# MPU-6050-HMC-5883.net
KiCad netlist of a schematic drawn in EAGLE
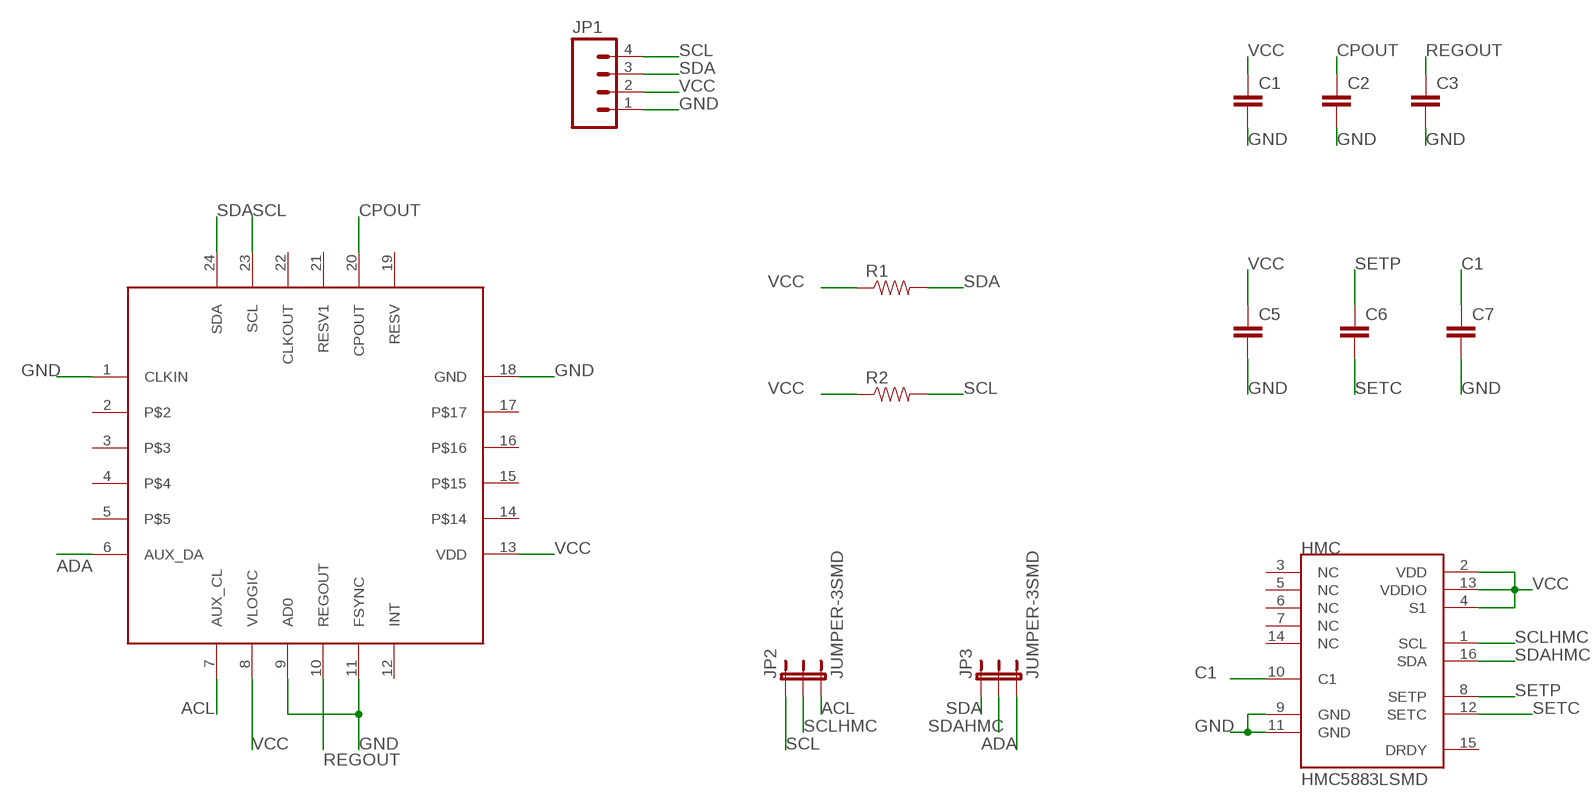
[diagram p0: schematic, sheet 1]

(export (version "E")
  (design (tool "Eeschema 10.0.6"))
  (components
    (comp (ref "C1")
      (value "CAP0603-CAP")
      (footprint "eagle-import:0603-CAP")
      (libsource (lib "eagle-import") (part "CAP0603-CAP"))
    )
    (comp (ref "C2")
      (value "CAP0603-CAP")
      (footprint "eagle-import:0603-CAP")
      (libsource (lib "eagle-import") (part "CAP0603-CAP"))
    )
    (comp (ref "C3")
      (value "CAP0603-CAP")
      (footprint "eagle-import:0603-CAP")
      (libsource (lib "eagle-import") (part "CAP0603-CAP"))
    )
    (comp (ref "C5")
      (value "CAP0603-CAP")
      (footprint "eagle-import:0603-CAP")
      (libsource (lib "eagle-import") (part "CAP0603-CAP"))
    )
    (comp (ref "C6")
      (value "CAP0603-CAP")
      (footprint "eagle-import:0603-CAP")
      (libsource (lib "eagle-import") (part "CAP0603-CAP"))
    )
    (comp (ref "C7")
      (value "CAP0603-CAP")
      (footprint "eagle-import:0603-CAP")
      (libsource (lib "eagle-import") (part "CAP0603-CAP"))
    )
    (comp (ref "HMC")
      (value "HMC5883LSMD")
      (footprint "eagle-import:16LPCC")
      (libsource (lib "eagle-import") (part "HMC5883LSMD"))
    )
    (comp (ref "JP1")
      (value "M04PTH")
      (footprint "eagle-import:1X04")
      (libsource (lib "eagle-import") (part "M04PTH"))
    )
    (comp (ref "JP2")
      (value "JUMPER-3SMD")
      (footprint "eagle-import:SJ_3")
      (libsource (lib "eagle-import") (part "JUMPER-3SMD"))
    )
    (comp (ref "JP3")
      (value "JUMPER-3SMD")
      (footprint "eagle-import:SJ_3")
      (libsource (lib "eagle-import") (part "JUMPER-3SMD"))
    )
    (comp (ref "MPU")
      (value "MPU-6050")
      (footprint "eagle-import:QFN-24")
      (libsource (lib "eagle-import") (part "MPU-6050"))
    )
    (comp (ref "R1")
      (value "RESISTOR0603-RES")
      (footprint "eagle-import:0603-RES")
      (libsource (lib "eagle-import") (part "RESISTOR0603-RES"))
    )
    (comp (ref "R2")
      (value "RESISTOR0603-RES")
      (footprint "eagle-import:0603-RES")
      (libsource (lib "eagle-import") (part "RESISTOR0603-RES"))
    )
  )
  (nets
    (net (code "1") (name "/ACL") (class "Default")
      (node (ref "JP2") (pin "3") (pinfunction "3_3") (pintype "passive"))
      (node (ref "MPU") (pin "7") (pinfunction "AUX_CL_7") (pintype "bidirectional"))
    )
    (net (code "2") (name "/ADA") (class "Default")
      (node (ref "JP3") (pin "3") (pinfunction "3_3") (pintype "passive"))
      (node (ref "MPU") (pin "6") (pinfunction "AUX_DA_6") (pintype "bidirectional"))
    )
    (net (code "3") (name "/C1") (class "Default")
      (node (ref "C7") (pin "1") (pinfunction "1_1") (pintype "passive"))
      (node (ref "HMC") (pin "10") (pinfunction "C1_10") (pintype "bidirectional"))
    )
    (net (code "4") (name "/CPOUT") (class "Default")
      (node (ref "C2") (pin "1") (pinfunction "1_1") (pintype "passive"))
      (node (ref "MPU") (pin "20") (pinfunction "CPOUT_20") (pintype "bidirectional"))
    )
    (net (code "5") (name "/GND") (class "Default")
      (node (ref "C1") (pin "2") (pinfunction "2_2") (pintype "passive"))
      (node (ref "C2") (pin "2") (pinfunction "2_2") (pintype "passive"))
      (node (ref "C3") (pin "2") (pinfunction "2_2") (pintype "passive"))
      (node (ref "C5") (pin "2") (pinfunction "2_2") (pintype "passive"))
      (node (ref "C7") (pin "2") (pinfunction "2_2") (pintype "passive"))
      (node (ref "HMC") (pin "11") (pinfunction "GND_11") (pintype "bidirectional"))
      (node (ref "HMC") (pin "9") (pinfunction "GND_9") (pintype "bidirectional"))
      (node (ref "JP1") (pin "1") (pinfunction "1_1") (pintype "passive"))
      (node (ref "MPU") (pin "1") (pinfunction "CLKIN_1") (pintype "bidirectional"))
      (node (ref "MPU") (pin "11") (pinfunction "FSYNC_11") (pintype "bidirectional"))
      (node (ref "MPU") (pin "18") (pinfunction "GND_18") (pintype "bidirectional"))
      (node (ref "MPU") (pin "9") (pinfunction "AD0_9") (pintype "bidirectional"))
    )
    (net (code "6") (name "/REGOUT") (class "Default")
      (node (ref "C3") (pin "1") (pinfunction "1_1") (pintype "passive"))
      (node (ref "MPU") (pin "10") (pinfunction "REGOUT_10") (pintype "bidirectional"))
    )
    (net (code "7") (name "/SCL") (class "Default")
      (node (ref "JP1") (pin "4") (pinfunction "4_4") (pintype "passive"))
      (node (ref "JP2") (pin "1") (pinfunction "1_1") (pintype "passive"))
      (node (ref "MPU") (pin "23") (pinfunction "SCL_23") (pintype "bidirectional"))
      (node (ref "R2") (pin "2") (pinfunction "2_2") (pintype "passive"))
    )
    (net (code "8") (name "/SCLHMC") (class "Default")
      (node (ref "HMC") (pin "1") (pinfunction "SCL_1") (pintype "bidirectional"))
      (node (ref "JP2") (pin "2") (pinfunction "2_2") (pintype "passive"))
    )
    (net (code "9") (name "/SDA") (class "Default")
      (node (ref "JP1") (pin "3") (pinfunction "3_3") (pintype "passive"))
      (node (ref "JP3") (pin "1") (pinfunction "1_1") (pintype "passive"))
      (node (ref "MPU") (pin "24") (pinfunction "SDA_24") (pintype "bidirectional"))
      (node (ref "R1") (pin "2") (pinfunction "2_2") (pintype "passive"))
    )
    (net (code "10") (name "/SDAHMC") (class "Default")
      (node (ref "HMC") (pin "16") (pinfunction "SDA_16") (pintype "bidirectional"))
      (node (ref "JP3") (pin "2") (pinfunction "2_2") (pintype "passive"))
    )
    (net (code "11") (name "/SETC") (class "Default")
      (node (ref "C6") (pin "2") (pinfunction "2_2") (pintype "passive"))
      (node (ref "HMC") (pin "12") (pinfunction "SETC_12") (pintype "bidirectional"))
    )
    (net (code "12") (name "/SETP") (class "Default")
      (node (ref "C6") (pin "1") (pinfunction "1_1") (pintype "passive"))
      (node (ref "HMC") (pin "8") (pinfunction "SETP_8") (pintype "bidirectional"))
    )
    (net (code "13") (name "/VCC") (class "Default")
      (node (ref "C1") (pin "1") (pinfunction "1_1") (pintype "passive"))
      (node (ref "C5") (pin "1") (pinfunction "1_1") (pintype "passive"))
      (node (ref "HMC") (pin "13") (pinfunction "VDDIO_13") (pintype "bidirectional"))
      (node (ref "HMC") (pin "2") (pinfunction "VDD_2") (pintype "bidirectional"))
      (node (ref "HMC") (pin "4") (pinfunction "S1_4") (pintype "bidirectional"))
      (node (ref "JP1") (pin "2") (pinfunction "2_2") (pintype "passive"))
      (node (ref "MPU") (pin "13") (pinfunction "VDD_13") (pintype "bidirectional"))
      (node (ref "MPU") (pin "8") (pinfunction "VLOGIC_8") (pintype "bidirectional"))
      (node (ref "R1") (pin "1") (pinfunction "1_1") (pintype "passive"))
      (node (ref "R2") (pin "1") (pinfunction "1_1") (pintype "passive"))
    )
    (net (code "14") (name "unconnected-(HMC-DRDY-Pad15)") (class "Default")
      (node (ref "HMC") (pin "15") (pinfunction "DRDY_15") (pintype "bidirectional"))
    )
    (net (code "15") (name "unconnected-(HMC-NC-Pad3)") (class "Default")
      (node (ref "HMC") (pin "3") (pinfunction "NC_3") (pintype "bidirectional"))
    )
    (net (code "16") (name "unconnected-(HMC-NC-Pad5)") (class "Default")
      (node (ref "HMC") (pin "5") (pinfunction "NC_5") (pintype "bidirectional"))
    )
    (net (code "17") (name "unconnected-(HMC-NC-Pad6)") (class "Default")
      (node (ref "HMC") (pin "6") (pinfunction "NC_6") (pintype "bidirectional"))
    )
    (net (code "18") (name "unconnected-(HMC-NC-Pad7)") (class "Default")
      (node (ref "HMC") (pin "7") (pinfunction "NC_7") (pintype "bidirectional"))
    )
    (net (code "19") (name "unconnected-(HMC-NC-Pad14)") (class "Default")
      (node (ref "HMC") (pin "14") (pinfunction "NC_14") (pintype "bidirectional"))
    )
    (net (code "20") (name "unconnected-(MPU-CLKOUT-Pad22)") (class "Default")
      (node (ref "MPU") (pin "22") (pinfunction "CLKOUT_22") (pintype "bidirectional"))
    )
    (net (code "21") (name "unconnected-(MPU-INT-Pad12)") (class "Default")
      (node (ref "MPU") (pin "12") (pinfunction "INT_12") (pintype "bidirectional"))
    )
    (net (code "22") (name "unconnected-(MPU-P$2-Pad2)") (class "Default")
      (node (ref "MPU") (pin "2") (pinfunction "P$2_2") (pintype "bidirectional"))
    )
    (net (code "23") (name "unconnected-(MPU-P$3-Pad3)") (class "Default")
      (node (ref "MPU") (pin "3") (pinfunction "P$3_3") (pintype "bidirectional"))
    )
    (net (code "24") (name "unconnected-(MPU-P$4-Pad4)") (class "Default")
      (node (ref "MPU") (pin "4") (pinfunction "P$4_4") (pintype "bidirectional"))
    )
    (net (code "25") (name "unconnected-(MPU-P$5-Pad5)") (class "Default")
      (node (ref "MPU") (pin "5") (pinfunction "P$5_5") (pintype "bidirectional"))
    )
    (net (code "26") (name "unconnected-(MPU-P$14-Pad14)") (class "Default")
      (node (ref "MPU") (pin "14") (pinfunction "P$14_14") (pintype "bidirectional"))
    )
    (net (code "27") (name "unconnected-(MPU-P$15-Pad15)") (class "Default")
      (node (ref "MPU") (pin "15") (pinfunction "P$15_15") (pintype "bidirectional"))
    )
    (net (code "28") (name "unconnected-(MPU-P$16-Pad16)") (class "Default")
      (node (ref "MPU") (pin "16") (pinfunction "P$16_16") (pintype "bidirectional"))
    )
    (net (code "29") (name "unconnected-(MPU-P$17-Pad17)") (class "Default")
      (node (ref "MPU") (pin "17") (pinfunction "P$17_17") (pintype "bidirectional"))
    )
    (net (code "30") (name "unconnected-(MPU-RESV-Pad19)") (class "Default")
      (node (ref "MPU") (pin "19") (pinfunction "RESV_19") (pintype "bidirectional"))
    )
    (net (code "31") (name "unconnected-(MPU-RESV1-Pad21)") (class "Default")
      (node (ref "MPU") (pin "21") (pinfunction "RESV1_21") (pintype "bidirectional"))
    )
  )
)
